# Cade.net
KiCad netlist of a schematic drawn in Altium Designer
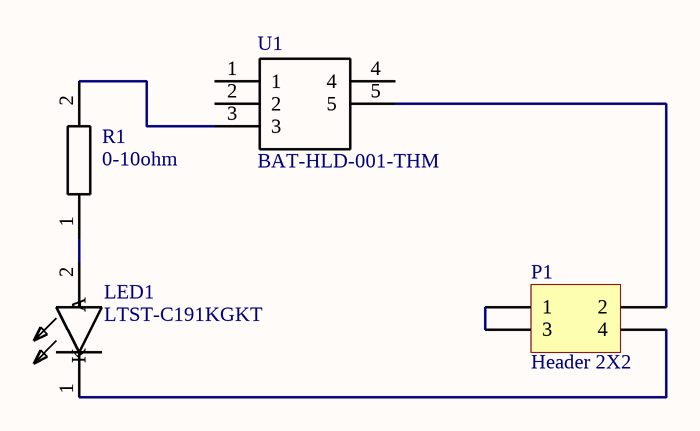
[diagram p0: Cade.SchDoc]

(export (version "E")
  (design (tool "Eeschema 10.0.6"))
  (components
    (comp (ref "LED1")
      (value "LTST-C191KGKT")
      (footprint "SamacSys:LEDC1608X55N")
      (description "LED")
      (fields
        (field (name "MOUSER PART NUMBER") "859-LTST-C191KGKT")
        (field (name "RS PART NUMBER") "6921010P")
      )
      (libsource (lib "*") (part "LTST-C191KGKT"))
    )
    (comp (ref "P1")
      (value "Header 2X2")
      (footprint "HDR2X2")
      (description "Header, 2-Pin, Dual row")
      (fields (field (name "PUBLISHER") "Altium Limited"))
      (libsource (lib "Miscellaneous Connectors") (part "Header 2X2"))
    )
    (comp (ref "R1")
      (value "0-10ohm")
      (footprint "SamacSys:RESC2012X60N")
      (description "Resistor")
      (fields
        (field (name "MANUFACTURER_PART_NUMBER") "CRCW0805160RFKEAHP")
        (field (name "MOUSER PART NUMBER") "71-CRCW0805160RFKEAH")
      )
      (libsource (lib "*") (part "CRCW0805160RFKEAHP"))
    )
    (comp (ref "U1")
      (value "BAT-HLD-001-THM")
      (footprint "SamacSys:BATHLD001THM")
      (description "Undefined or Miscellaneous")
      (fields (field (name "MOUSER PART NUMBER") "712-BAT-HLD-001-THM"))
      (libsource (lib "*") (part "BAT-HLD-001-THM"))
    )
  )
  (nets
    (net (code "1") (name "Net-(LED1-A)") (class "Default")
      (node (ref "LED1") (pin "2") (pinfunction "A_2") (pintype "passive"))
      (node (ref "R1") (pin "1") (pinfunction "1_1") (pintype "passive"))
    )
    (net (code "2") (name "Net-(LED1-K)") (class "Default")
      (node (ref "LED1") (pin "1") (pinfunction "K_1") (pintype "passive"))
      (node (ref "P1") (pin "4") (pinfunction "4_4") (pintype "passive"))
    )
    (net (code "3") (name "Net-(P1-Pad1)") (class "Default")
      (node (ref "P1") (pin "1") (pinfunction "1_1") (pintype "passive"))
      (node (ref "P1") (pin "3") (pinfunction "3_3") (pintype "passive"))
    )
    (net (code "4") (name "Net-(P1-Pad2)") (class "Default")
      (node (ref "P1") (pin "2") (pinfunction "2_2") (pintype "passive"))
      (node (ref "U1") (pin "5") (pinfunction "5_5") (pintype "passive"))
    )
    (net (code "5") (name "Net-(R1-Pad2)") (class "Default")
      (node (ref "R1") (pin "2") (pinfunction "2_2") (pintype "passive"))
      (node (ref "U1") (pin "3") (pinfunction "3_3") (pintype "passive"))
    )
    (net (code "6") (name "unconnected-(U1-Pad1)") (class "Default")
      (node (ref "U1") (pin "1") (pinfunction "1_1") (pintype "passive"))
    )
    (net (code "7") (name "unconnected-(U1-Pad2)") (class "Default")
      (node (ref "U1") (pin "2") (pinfunction "2_2") (pintype "passive"))
    )
    (net (code "8") (name "unconnected-(U1-Pad4)") (class "Default")
      (node (ref "U1") (pin "4") (pinfunction "4_4") (pintype "passive"))
    )
  )
)
